# distortion-noise-and-ring-modulator-v1_0.net
KiCad netlist of a schematic drawn in EAGLE
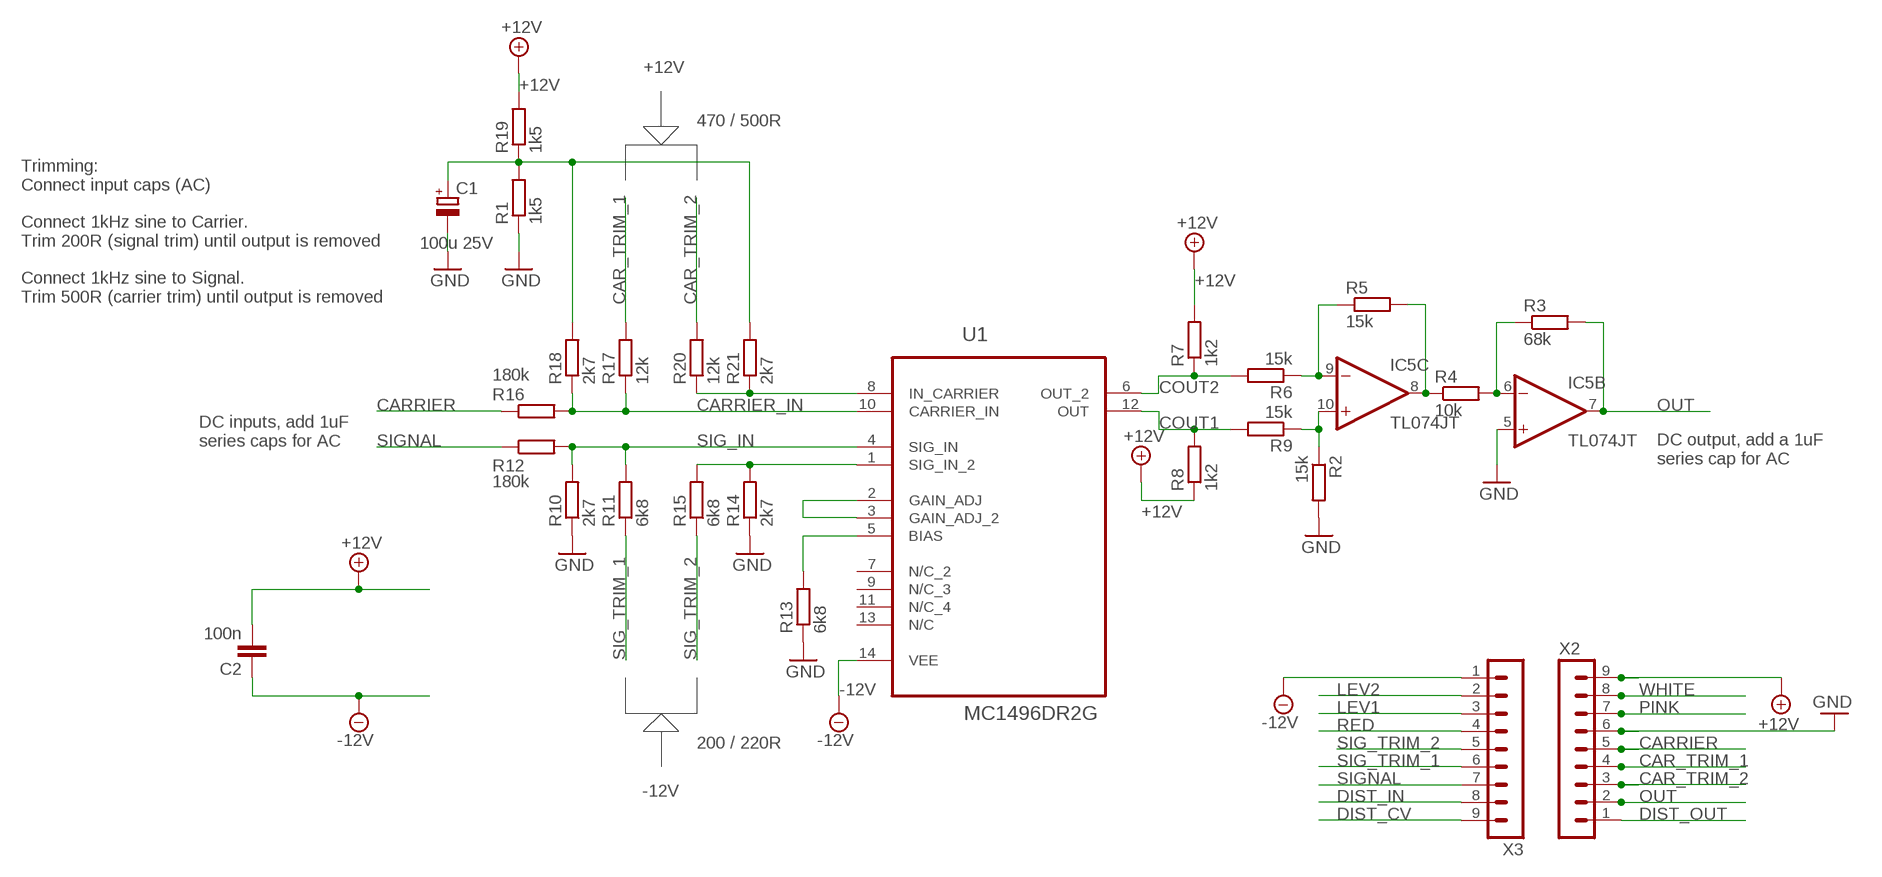
[diagram p0: schematic, sheet 1]
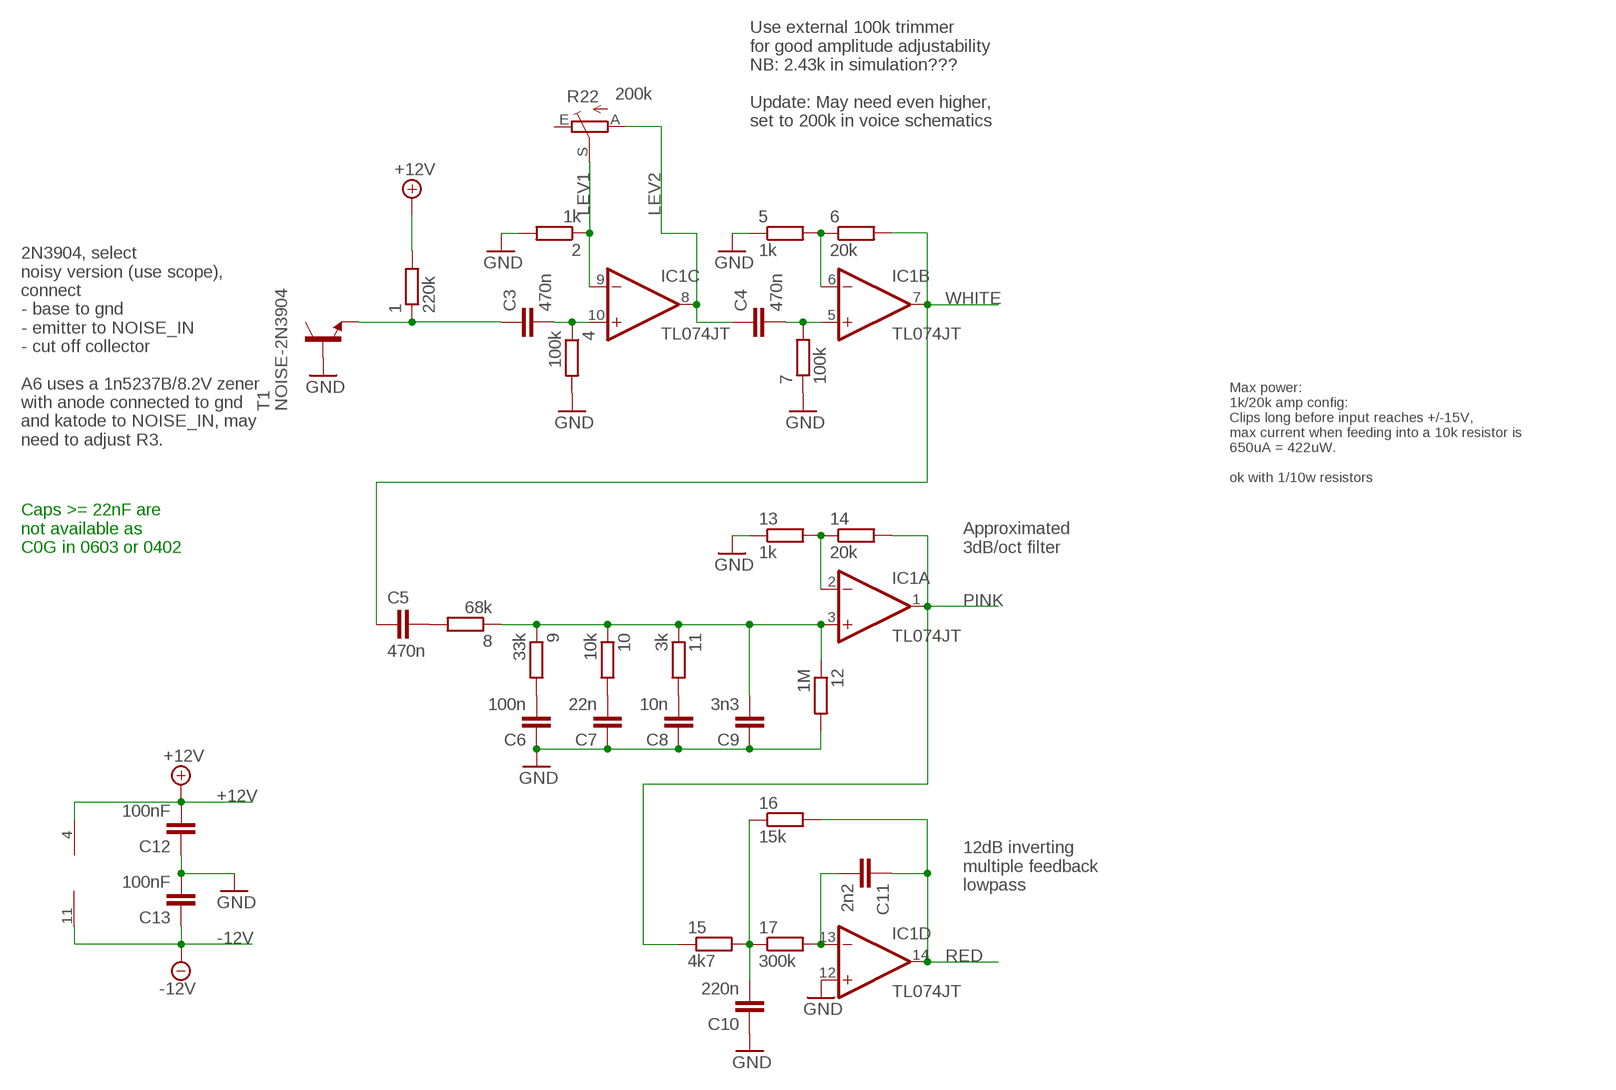
[diagram p1: schematic, sheet 2]
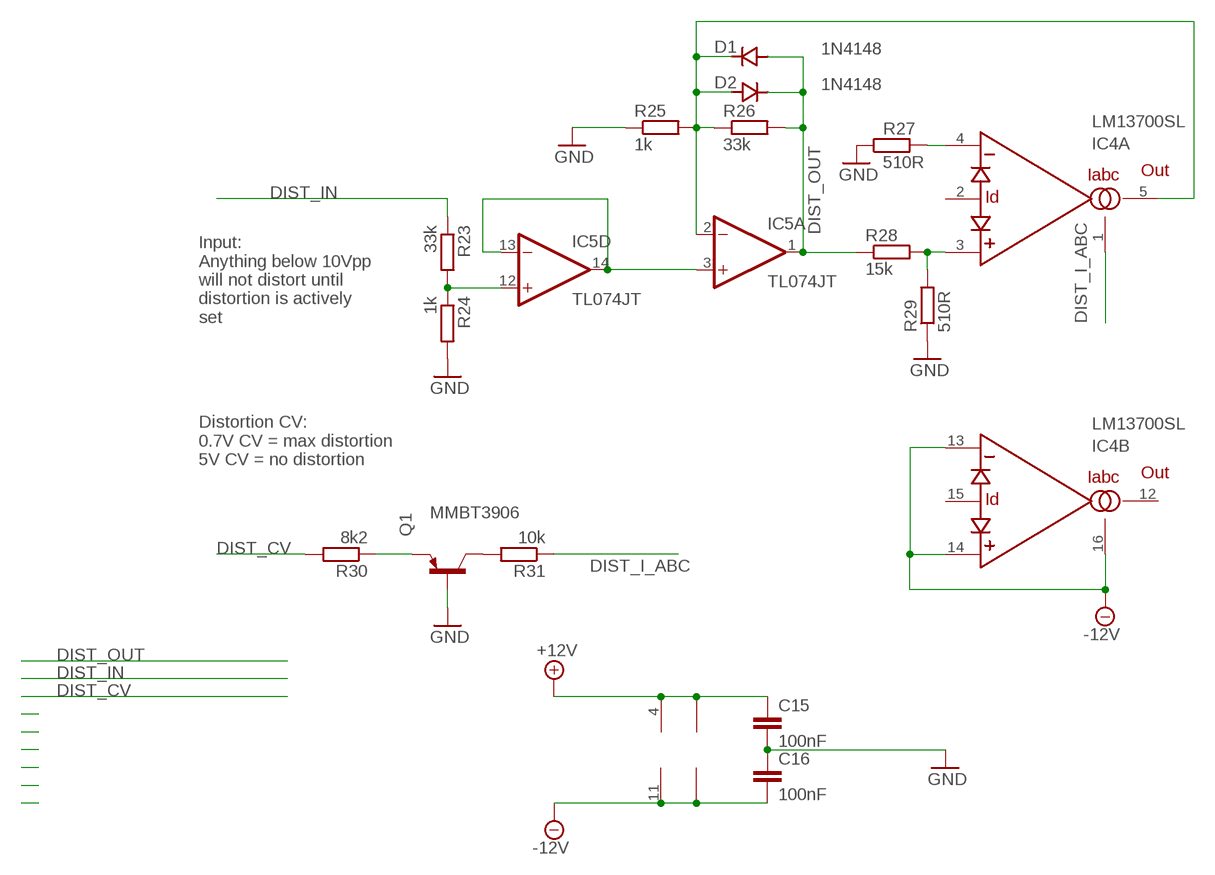
[diagram p2: schematic, sheet 3]

(export (version "E")
  (design (tool "Eeschema 10.0.6"))
  (components
    (comp (ref "1")
      (value "220k")
      (footprint "eagle-import:R0402")
      (libsource (lib "eagle-import") (part "R-EU_R0402"))
    )
    (comp (ref "2")
      (value "1k")
      (footprint "eagle-import:R0402")
      (libsource (lib "eagle-import") (part "R-EU_R0402"))
    )
    (comp (ref "4")
      (value "100k")
      (footprint "eagle-import:R0402")
      (libsource (lib "eagle-import") (part "R-EU_R0402"))
    )
    (comp (ref "5")
      (value "1k")
      (footprint "eagle-import:R0402")
      (libsource (lib "eagle-import") (part "R-EU_R0402"))
    )
    (comp (ref "6")
      (value "20k")
      (footprint "eagle-import:R0402")
      (libsource (lib "eagle-import") (part "R-EU_R0402"))
    )
    (comp (ref "7")
      (value "100k")
      (footprint "eagle-import:R0402")
      (libsource (lib "eagle-import") (part "R-EU_R0402"))
    )
    (comp (ref "8")
      (value "68k")
      (footprint "eagle-import:R0402")
      (libsource (lib "eagle-import") (part "R-EU_R0402"))
    )
    (comp (ref "9")
      (value "33k")
      (footprint "eagle-import:R0402")
      (libsource (lib "eagle-import") (part "R-EU_R0402"))
    )
    (comp (ref "10")
      (value "10k")
      (footprint "eagle-import:R0402")
      (libsource (lib "eagle-import") (part "R-EU_R0402"))
    )
    (comp (ref "11")
      (value "3k")
      (footprint "eagle-import:R0402")
      (libsource (lib "eagle-import") (part "R-EU_R0402"))
    )
    (comp (ref "12")
      (value "1M")
      (footprint "eagle-import:R0402")
      (libsource (lib "eagle-import") (part "R-EU_R0402"))
    )
    (comp (ref "13")
      (value "1k")
      (footprint "eagle-import:R0402")
      (libsource (lib "eagle-import") (part "R-EU_R0402"))
    )
    (comp (ref "14")
      (value "20k")
      (footprint "eagle-import:R0402")
      (libsource (lib "eagle-import") (part "R-EU_R0402"))
    )
    (comp (ref "15")
      (value "4k7")
      (footprint "eagle-import:R0402")
      (libsource (lib "eagle-import") (part "R-EU_R0402"))
    )
    (comp (ref "16")
      (value "15k")
      (footprint "eagle-import:R0402")
      (libsource (lib "eagle-import") (part "R-EU_R0402"))
    )
    (comp (ref "17")
      (value "300k")
      (footprint "eagle-import:R0402")
      (libsource (lib "eagle-import") (part "R-EU_R0402"))
    )
    (comp (ref "C3")
      (value "470n")
      (footprint "eagle-import:C0402-J")
      (libsource (lib "eagle-import") (part "C-EU-J"))
    )
    (comp (ref "C4")
      (value "470n")
      (footprint "eagle-import:C0402-J")
      (libsource (lib "eagle-import") (part "C-EU-J"))
    )
    (comp (ref "C5")
      (value "470n")
      (footprint "eagle-import:C0402-J")
      (libsource (lib "eagle-import") (part "C-EU-J"))
    )
    (comp (ref "C6")
      (value "100n")
      (footprint "eagle-import:C0402-J")
      (libsource (lib "eagle-import") (part "C-EU-J"))
    )
    (comp (ref "C7")
      (value "22n")
      (footprint "eagle-import:C0402-J")
      (libsource (lib "eagle-import") (part "C-EU-J"))
    )
    (comp (ref "C8")
      (value "10n")
      (footprint "eagle-import:C0402-J")
      (libsource (lib "eagle-import") (part "C-EU-J"))
    )
    (comp (ref "C9")
      (value "3n3")
      (footprint "eagle-import:C0402-J")
      (libsource (lib "eagle-import") (part "C-EU-J"))
    )
    (comp (ref "C10")
      (value "220n")
      (footprint "eagle-import:C0402-J")
      (libsource (lib "eagle-import") (part "C-EU-J"))
    )
    (comp (ref "C11")
      (value "2n2")
      (footprint "eagle-import:C0402-J")
      (libsource (lib "eagle-import") (part "C-EU-J"))
    )
    (comp (ref "C12")
      (value "100nF")
      (footprint "eagle-import:C0402-J")
      (libsource (lib "eagle-import") (part "C-EU-J"))
    )
    (comp (ref "C13")
      (value "100nF")
      (footprint "eagle-import:C0402-J")
      (libsource (lib "eagle-import") (part "C-EU-J"))
    )
    (comp (ref "IC1")
      (value "TL074JT")
      (footprint "eagle-import:TSSOP14J")
      (libsource (lib "eagle-import") (part "TL074JT"))
    )
    (comp (ref "R22")
      (value "200k")
      (footprint "eagle-import:S64W")
      (libsource (lib "eagle-import") (part "TRIM_EU-S64W"))
    )
    (comp (ref "T1")
      (value "NOISE-2N3904")
      (footprint "eagle-import:NOISE-2N3904-J")
      (libsource (lib "eagle-import") (part "NOISE-2N3904"))
    )
    (comp (ref "C1")
      (value "100u 25V")
      (footprint "eagle-import:UD-4X5,8_NICHICON")
      (libsource (lib "eagle-import") (part "CPOL-EUUD-4X5,8"))
    )
    (comp (ref "C2")
      (value "100n")
      (footprint "eagle-import:C0402-J")
      (libsource (lib "eagle-import") (part "C-EU-J"))
    )
    (comp (ref "IC5")
      (value "TL074JT")
      (footprint "eagle-import:TSSOP14J")
      (libsource (lib "eagle-import") (part "TL074JT"))
    )
    (comp (ref "R1")
      (value "1k5")
      (footprint "eagle-import:R0402")
      (libsource (lib "eagle-import") (part "R-EU_R0402"))
    )
    (comp (ref "R2")
      (value "15k")
      (footprint "eagle-import:R0402")
      (libsource (lib "eagle-import") (part "R-EU_R0402"))
    )
    (comp (ref "R3")
      (value "68k")
      (footprint "eagle-import:R0402")
      (libsource (lib "eagle-import") (part "R-EU_R0402"))
    )
    (comp (ref "R4")
      (value "10k")
      (footprint "eagle-import:R0402")
      (libsource (lib "eagle-import") (part "R-EU_R0402"))
    )
    (comp (ref "R5")
      (value "15k")
      (footprint "eagle-import:R0402")
      (libsource (lib "eagle-import") (part "R-EU_R0402"))
    )
    (comp (ref "R6")
      (value "15k")
      (footprint "eagle-import:R0402")
      (libsource (lib "eagle-import") (part "R-EU_R0402"))
    )
    (comp (ref "R7")
      (value "1k2")
      (footprint "eagle-import:R0402")
      (libsource (lib "eagle-import") (part "R-EU_R0402"))
    )
    (comp (ref "R8")
      (value "1k2")
      (footprint "eagle-import:R0402")
      (libsource (lib "eagle-import") (part "R-EU_R0402"))
    )
    (comp (ref "R9")
      (value "15k")
      (footprint "eagle-import:R0402")
      (libsource (lib "eagle-import") (part "R-EU_R0402"))
    )
    (comp (ref "R10")
      (value "2k7")
      (footprint "eagle-import:R0402")
      (libsource (lib "eagle-import") (part "R-EU_R0402"))
    )
    (comp (ref "R11")
      (value "6k8")
      (footprint "eagle-import:R0402")
      (libsource (lib "eagle-import") (part "R-EU_R0402"))
    )
    (comp (ref "R12")
      (value "180k")
      (footprint "eagle-import:R0402")
      (libsource (lib "eagle-import") (part "R-EU_R0402"))
    )
    (comp (ref "R13")
      (value "6k8")
      (footprint "eagle-import:R0402")
      (libsource (lib "eagle-import") (part "R-EU_R0402"))
    )
    (comp (ref "R14")
      (value "2k7")
      (footprint "eagle-import:R0402")
      (libsource (lib "eagle-import") (part "R-EU_R0402"))
    )
    (comp (ref "R15")
      (value "6k8")
      (footprint "eagle-import:R0402")
      (libsource (lib "eagle-import") (part "R-EU_R0402"))
    )
    (comp (ref "R16")
      (value "180k")
      (footprint "eagle-import:R0402")
      (libsource (lib "eagle-import") (part "R-EU_R0402"))
    )
    (comp (ref "R17")
      (value "12k")
      (footprint "eagle-import:R0402")
      (libsource (lib "eagle-import") (part "R-EU_R0402"))
    )
    (comp (ref "R18")
      (value "2k7")
      (footprint "eagle-import:R0402")
      (libsource (lib "eagle-import") (part "R-EU_R0402"))
    )
    (comp (ref "R19")
      (value "1k5")
      (footprint "eagle-import:R0402")
      (libsource (lib "eagle-import") (part "R-EU_R0402"))
    )
    (comp (ref "R20")
      (value "12k")
      (footprint "eagle-import:R0402")
      (libsource (lib "eagle-import") (part "R-EU_R0402"))
    )
    (comp (ref "R21")
      (value "2k7")
      (footprint "eagle-import:R0402")
      (libsource (lib "eagle-import") (part "R-EU_R0402"))
    )
    (comp (ref "U1")
      (value "MC1496DR2G")
      (footprint "eagle-import:SOIC127P600X175-14N")
      (libsource (lib "eagle-import") (part "MC1496DR2G"))
    )
    (comp (ref "X2")
      (value "MA09-1JN")
      (footprint "eagle-import:MA09N-1J")
      (libsource (lib "eagle-import") (part "MA09-1JN"))
    )
    (comp (ref "X3")
      (value "MA09-1JN")
      (footprint "eagle-import:MA09N-1J")
      (libsource (lib "eagle-import") (part "MA09-1JN"))
    )
    (comp (ref "C15")
      (value "100nF")
      (footprint "eagle-import:C0402-J")
      (libsource (lib "eagle-import") (part "C-EU-J"))
    )
    (comp (ref "C16")
      (value "100nF")
      (footprint "eagle-import:C0402-J")
      (libsource (lib "eagle-import") (part "C-EU-J"))
    )
    (comp (ref "D1")
      (value "1N4148")
      (footprint "eagle-import:SOD323J")
      (libsource (lib "eagle-import") (part "1N4148SOD323"))
    )
    (comp (ref "D2")
      (value "1N4148")
      (footprint "eagle-import:SOD323J")
      (libsource (lib "eagle-import") (part "1N4148SOD323"))
    )
    (comp (ref "IC4")
      (value "LM13700SL")
      (footprint "eagle-import:SO16-NARROW-J")
      (libsource (lib "eagle-import") (part "LM13700SL"))
    )
    (comp (ref "Q1")
      (value "MMBT3906")
      (footprint "eagle-import:SOT23-BEC")
      (libsource (lib "eagle-import") (part "MMBT3906SMDLT1"))
    )
    (comp (ref "R23")
      (value "33k")
      (footprint "eagle-import:R0402")
      (libsource (lib "eagle-import") (part "R-EU_R0402"))
    )
    (comp (ref "R24")
      (value "1k")
      (footprint "eagle-import:R0402")
      (libsource (lib "eagle-import") (part "R-EU_R0402"))
    )
    (comp (ref "R25")
      (value "1k")
      (footprint "eagle-import:R0402")
      (libsource (lib "eagle-import") (part "R-EU_R0402"))
    )
    (comp (ref "R26")
      (value "33k")
      (footprint "eagle-import:R0402")
      (libsource (lib "eagle-import") (part "R-EU_R0402"))
    )
    (comp (ref "R27")
      (value "510R")
      (footprint "eagle-import:R0402")
      (libsource (lib "eagle-import") (part "R-EU_R0402"))
    )
    (comp (ref "R28")
      (value "15k")
      (footprint "eagle-import:R0402")
      (libsource (lib "eagle-import") (part "R-EU_R0402"))
    )
    (comp (ref "R29")
      (value "510R")
      (footprint "eagle-import:R0402")
      (libsource (lib "eagle-import") (part "R-EU_R0402"))
    )
    (comp (ref "R30")
      (value "8k2")
      (footprint "eagle-import:R0402")
      (libsource (lib "eagle-import") (part "R-EU_R0402"))
    )
    (comp (ref "R31")
      (value "10k")
      (footprint "eagle-import:R0402")
      (libsource (lib "eagle-import") (part "R-EU_R0402"))
    )
  )
  (nets
    (net (code "1") (name "+12V") (class "Default")
      (node (ref "1") (pin "2") (pinfunction "2_2") (pintype "passive"))
      (node (ref "C12") (pin "2") (pinfunction "2_2") (pintype "passive"))
      (node (ref "C15") (pin "1") (pinfunction "1_1") (pintype "passive"))
      (node (ref "C2") (pin "2") (pinfunction "2_2") (pintype "passive"))
      (node (ref "IC1") (pin "4") (pinfunction "V+_4") (pintype "power_in"))
      (node (ref "IC4") (pin "11") (pinfunction "V+_11") (pintype "bidirectional"))
      (node (ref "IC5") (pin "4") (pinfunction "V+_4") (pintype "power_in"))
      (node (ref "R19") (pin "2") (pinfunction "2_2") (pintype "passive"))
      (node (ref "R7") (pin "2") (pinfunction "2_2") (pintype "passive"))
      (node (ref "R8") (pin "1") (pinfunction "1_1") (pintype "passive"))
      (node (ref "X2") (pin "9") (pinfunction "9_9") (pintype "passive"))
    )
    (net (code "2") (name "-12V") (class "Default")
      (node (ref "C13") (pin "1") (pinfunction "1_1") (pintype "passive"))
      (node (ref "C16") (pin "2") (pinfunction "2_2") (pintype "passive"))
      (node (ref "C2") (pin "1") (pinfunction "1_1") (pintype "passive"))
      (node (ref "IC1") (pin "11") (pinfunction "V-_11") (pintype "power_in"))
      (node (ref "IC4") (pin "13") (pinfunction "-IN_13") (pintype "bidirectional"))
      (node (ref "IC4") (pin "14") (pinfunction "+IN_14") (pintype "bidirectional"))
      (node (ref "IC4") (pin "16") (pinfunction "IABC_16") (pintype "bidirectional"))
      (node (ref "IC4") (pin "6") (pinfunction "V-_6") (pintype "bidirectional"))
      (node (ref "IC5") (pin "11") (pinfunction "V-_11") (pintype "power_in"))
      (node (ref "U1") (pin "14") (pinfunction "VEE_14") (pintype "passive"))
      (node (ref "X3") (pin "1") (pinfunction "1_1") (pintype "passive"))
    )
    (net (code "3") (name "CARRIER") (class "Default")
      (node (ref "R16") (pin "1") (pinfunction "1_1") (pintype "passive"))
      (node (ref "X2") (pin "5") (pinfunction "5_5") (pintype "passive"))
    )
    (net (code "4") (name "CARRIER_IN") (class "Default")
      (node (ref "R16") (pin "2") (pinfunction "2_2") (pintype "passive"))
      (node (ref "R17") (pin "1") (pinfunction "1_1") (pintype "passive"))
      (node (ref "R18") (pin "1") (pinfunction "1_1") (pintype "passive"))
      (node (ref "U1") (pin "10") (pinfunction "CARRIER_IN_10") (pintype "power_in"))
    )
    (net (code "5") (name "CAR_TRIM_1") (class "Default")
      (node (ref "R17") (pin "2") (pinfunction "2_2") (pintype "passive"))
      (node (ref "X2") (pin "4") (pinfunction "4_4") (pintype "passive"))
    )
    (net (code "6") (name "CAR_TRIM_2") (class "Default")
      (node (ref "R20") (pin "2") (pinfunction "2_2") (pintype "passive"))
      (node (ref "X2") (pin "3") (pinfunction "3_3") (pintype "passive"))
    )
    (net (code "7") (name "COUT1") (class "Default")
      (node (ref "R8") (pin "2") (pinfunction "2_2") (pintype "passive"))
      (node (ref "R9") (pin "2") (pinfunction "2_2") (pintype "passive"))
      (node (ref "U1") (pin "12") (pinfunction "OUT_12") (pintype "output"))
    )
    (net (code "8") (name "COUT2") (class "Default")
      (node (ref "R6") (pin "2") (pinfunction "2_2") (pintype "passive"))
      (node (ref "R7") (pin "1") (pinfunction "1_1") (pintype "passive"))
      (node (ref "U1") (pin "6") (pinfunction "OUT_2_6") (pintype "output"))
    )
    (net (code "9") (name "DIST_CV") (class "Default")
      (node (ref "R30") (pin "2") (pinfunction "2_2") (pintype "passive"))
      (node (ref "X3") (pin "9") (pinfunction "9_9") (pintype "passive"))
    )
    (net (code "10") (name "DIST_IN") (class "Default")
      (node (ref "R23") (pin "1") (pinfunction "1_1") (pintype "passive"))
      (node (ref "X3") (pin "8") (pinfunction "8_8") (pintype "passive"))
    )
    (net (code "11") (name "DIST_I_ABC") (class "Default")
      (node (ref "IC4") (pin "1") (pinfunction "IABC_1") (pintype "bidirectional"))
      (node (ref "R31") (pin "1") (pinfunction "1_1") (pintype "passive"))
    )
    (net (code "12") (name "DIST_OUT") (class "Default")
      (node (ref "D1") (pin "2") (pinfunction "A_2") (pintype "passive"))
      (node (ref "D2") (pin "1") (pinfunction "C_1") (pintype "passive"))
      (node (ref "IC5") (pin "1") (pinfunction "OUT_1") (pintype "output"))
      (node (ref "R26") (pin "2") (pinfunction "2_2") (pintype "passive"))
      (node (ref "R28") (pin "1") (pinfunction "1_1") (pintype "passive"))
      (node (ref "X2") (pin "1") (pinfunction "1_1") (pintype "passive"))
    )
    (net (code "13") (name "GND") (class "Default")
      (node (ref "12") (pin "2") (pinfunction "2_2") (pintype "passive"))
      (node (ref "13") (pin "1") (pinfunction "1_1") (pintype "passive"))
      (node (ref "2") (pin "2") (pinfunction "2_2") (pintype "passive"))
      (node (ref "4") (pin "2") (pinfunction "2_2") (pintype "passive"))
      (node (ref "5") (pin "1") (pinfunction "1_1") (pintype "passive"))
      (node (ref "7") (pin "1") (pinfunction "1_1") (pintype "passive"))
      (node (ref "C1") (pin "-") (pinfunction "-_-") (pintype "passive"))
      (node (ref "C10") (pin "1") (pinfunction "1_1") (pintype "passive"))
      (node (ref "C12") (pin "1") (pinfunction "1_1") (pintype "passive"))
      (node (ref "C13") (pin "2") (pinfunction "2_2") (pintype "passive"))
      (node (ref "C15") (pin "2") (pinfunction "2_2") (pintype "passive"))
      (node (ref "C16") (pin "1") (pinfunction "1_1") (pintype "passive"))
      (node (ref "C6") (pin "1") (pinfunction "1_1") (pintype "passive"))
      (node (ref "C7") (pin "1") (pinfunction "1_1") (pintype "passive"))
      (node (ref "C8") (pin "1") (pinfunction "1_1") (pintype "passive"))
      (node (ref "C9") (pin "1") (pinfunction "1_1") (pintype "passive"))
      (node (ref "IC1") (pin "12") (pinfunction "+IN_12") (pintype "input"))
      (node (ref "IC5") (pin "5") (pinfunction "+IN_5") (pintype "input"))
      (node (ref "Q1") (pin "B") (pinfunction "B_B") (pintype "passive"))
      (node (ref "R1") (pin "1") (pinfunction "1_1") (pintype "passive"))
      (node (ref "R10") (pin "1") (pinfunction "1_1") (pintype "passive"))
      (node (ref "R13") (pin "1") (pinfunction "1_1") (pintype "passive"))
      (node (ref "R14") (pin "1") (pinfunction "1_1") (pintype "passive"))
      (node (ref "R2") (pin "2") (pinfunction "2_2") (pintype "passive"))
      (node (ref "R24") (pin "2") (pinfunction "2_2") (pintype "passive"))
      (node (ref "R25") (pin "1") (pinfunction "1_1") (pintype "passive"))
      (node (ref "R27") (pin "1") (pinfunction "1_1") (pintype "passive"))
      (node (ref "R29") (pin "1") (pinfunction "1_1") (pintype "passive"))
      (node (ref "T1") (pin "B") (pinfunction "B_B") (pintype "passive"))
      (node (ref "X2") (pin "6") (pinfunction "6_6") (pintype "passive"))
    )
    (net (code "14") (name "LEV1") (class "Default")
      (node (ref "2") (pin "1") (pinfunction "1_1") (pintype "passive"))
      (node (ref "IC1") (pin "9") (pinfunction "-IN_9") (pintype "input"))
      (node (ref "R22") (pin "S") (pinfunction "S_S") (pintype "passive"))
      (node (ref "X3") (pin "3") (pinfunction "3_3") (pintype "passive"))
    )
    (net (code "15") (name "LEV2") (class "Default")
      (node (ref "C4") (pin "1") (pinfunction "1_1") (pintype "passive"))
      (node (ref "IC1") (pin "8") (pinfunction "OUT_8") (pintype "output"))
      (node (ref "R22") (pin "A") (pinfunction "A_A") (pintype "passive"))
      (node (ref "X3") (pin "2") (pinfunction "2_2") (pintype "passive"))
    )
    (net (code "16") (name "Net-(1-Pad1)") (class "Default")
      (node (ref "1") (pin "1") (pinfunction "1_1") (pintype "passive"))
      (node (ref "C3") (pin "1") (pinfunction "1_1") (pintype "passive"))
      (node (ref "T1") (pin "E") (pinfunction "E_E") (pintype "passive"))
    )
    (net (code "17") (name "Net-(8-Pad2)") (class "Default")
      (node (ref "8") (pin "2") (pinfunction "2_2") (pintype "passive"))
      (node (ref "C5") (pin "2") (pinfunction "2_2") (pintype "passive"))
    )
    (net (code "18") (name "Net-(9-Pad2)") (class "Default")
      (node (ref "9") (pin "2") (pinfunction "2_2") (pintype "passive"))
      (node (ref "C6") (pin "2") (pinfunction "2_2") (pintype "passive"))
    )
    (net (code "19") (name "Net-(10-Pad2)") (class "Default")
      (node (ref "10") (pin "2") (pinfunction "2_2") (pintype "passive"))
      (node (ref "C7") (pin "2") (pinfunction "2_2") (pintype "passive"))
    )
    (net (code "20") (name "Net-(11-Pad2)") (class "Default")
      (node (ref "11") (pin "2") (pinfunction "2_2") (pintype "passive"))
      (node (ref "C8") (pin "2") (pinfunction "2_2") (pintype "passive"))
    )
    (net (code "21") (name "Net-(15-Pad2)") (class "Default")
      (node (ref "15") (pin "2") (pinfunction "2_2") (pintype "passive"))
      (node (ref "16") (pin "1") (pinfunction "1_1") (pintype "passive"))
      (node (ref "17") (pin "1") (pinfunction "1_1") (pintype "passive"))
      (node (ref "C10") (pin "2") (pinfunction "2_2") (pintype "passive"))
    )
    (net (code "22") (name "Net-(C1-Pad+)") (class "Default")
      (node (ref "C1") (pin "+") (pinfunction "+_+") (pintype "passive"))
      (node (ref "R1") (pin "2") (pinfunction "2_2") (pintype "passive"))
      (node (ref "R18") (pin "2") (pinfunction "2_2") (pintype "passive"))
      (node (ref "R19") (pin "1") (pinfunction "1_1") (pintype "passive"))
      (node (ref "R21") (pin "2") (pinfunction "2_2") (pintype "passive"))
    )
    (net (code "23") (name "Net-(D1-C)") (class "Default")
      (node (ref "D1") (pin "1") (pinfunction "C_1") (pintype "passive"))
      (node (ref "D2") (pin "2") (pinfunction "A_2") (pintype "passive"))
      (node (ref "IC4") (pin "5") (pinfunction "OUT_5") (pintype "bidirectional"))
      (node (ref "IC5") (pin "2") (pinfunction "-IN_2") (pintype "input"))
      (node (ref "R25") (pin "2") (pinfunction "2_2") (pintype "passive"))
      (node (ref "R26") (pin "1") (pinfunction "1_1") (pintype "passive"))
    )
    (net (code "24") (name "Net-(IC1A-+IN)") (class "Default")
      (node (ref "10") (pin "1") (pinfunction "1_1") (pintype "passive"))
      (node (ref "11") (pin "1") (pinfunction "1_1") (pintype "passive"))
      (node (ref "12") (pin "1") (pinfunction "1_1") (pintype "passive"))
      (node (ref "8") (pin "1") (pinfunction "1_1") (pintype "passive"))
      (node (ref "9") (pin "1") (pinfunction "1_1") (pintype "passive"))
      (node (ref "C9") (pin "2") (pinfunction "2_2") (pintype "passive"))
      (node (ref "IC1") (pin "3") (pinfunction "+IN_3") (pintype "input"))
    )
    (net (code "25") (name "Net-(IC1A--IN)") (class "Default")
      (node (ref "13") (pin "2") (pinfunction "2_2") (pintype "passive"))
      (node (ref "14") (pin "1") (pinfunction "1_1") (pintype "passive"))
      (node (ref "IC1") (pin "2") (pinfunction "-IN_2") (pintype "input"))
    )
    (net (code "26") (name "Net-(IC1B-+IN)") (class "Default")
      (node (ref "7") (pin "2") (pinfunction "2_2") (pintype "passive"))
      (node (ref "C4") (pin "2") (pinfunction "2_2") (pintype "passive"))
      (node (ref "IC1") (pin "5") (pinfunction "+IN_5") (pintype "input"))
    )
    (net (code "27") (name "Net-(IC1B--IN)") (class "Default")
      (node (ref "5") (pin "2") (pinfunction "2_2") (pintype "passive"))
      (node (ref "6") (pin "1") (pinfunction "1_1") (pintype "passive"))
      (node (ref "IC1") (pin "6") (pinfunction "-IN_6") (pintype "input"))
    )
    (net (code "28") (name "Net-(IC1C-+IN)") (class "Default")
      (node (ref "4") (pin "1") (pinfunction "1_1") (pintype "passive"))
      (node (ref "C3") (pin "2") (pinfunction "2_2") (pintype "passive"))
      (node (ref "IC1") (pin "10") (pinfunction "+IN_10") (pintype "input"))
    )
    (net (code "29") (name "Net-(IC1D--IN)") (class "Default")
      (node (ref "17") (pin "2") (pinfunction "2_2") (pintype "passive"))
      (node (ref "C11") (pin "2") (pinfunction "2_2") (pintype "passive"))
      (node (ref "IC1") (pin "13") (pinfunction "-IN_13") (pintype "input"))
    )
    (net (code "30") (name "Net-(IC4A-+IN)") (class "Default")
      (node (ref "IC4") (pin "3") (pinfunction "+IN_3") (pintype "bidirectional"))
      (node (ref "R28") (pin "2") (pinfunction "2_2") (pintype "passive"))
      (node (ref "R29") (pin "2") (pinfunction "2_2") (pintype "passive"))
    )
    (net (code "31") (name "Net-(IC4A--IN)") (class "Default")
      (node (ref "IC4") (pin "4") (pinfunction "-IN_4") (pintype "bidirectional"))
      (node (ref "R27") (pin "2") (pinfunction "2_2") (pintype "passive"))
    )
    (net (code "32") (name "Net-(IC5A-+IN)") (class "Default")
      (node (ref "IC5") (pin "13") (pinfunction "-IN_13") (pintype "input"))
      (node (ref "IC5") (pin "14") (pinfunction "OUT_14") (pintype "output"))
      (node (ref "IC5") (pin "3") (pinfunction "+IN_3") (pintype "input"))
    )
    (net (code "33") (name "Net-(IC5B--IN)") (class "Default")
      (node (ref "IC5") (pin "6") (pinfunction "-IN_6") (pintype "input"))
      (node (ref "R3") (pin "1") (pinfunction "1_1") (pintype "passive"))
      (node (ref "R4") (pin "2") (pinfunction "2_2") (pintype "passive"))
    )
    (net (code "34") (name "Net-(IC5C-+IN)") (class "Default")
      (node (ref "IC5") (pin "10") (pinfunction "+IN_10") (pintype "input"))
      (node (ref "R2") (pin "1") (pinfunction "1_1") (pintype "passive"))
      (node (ref "R9") (pin "1") (pinfunction "1_1") (pintype "passive"))
    )
    (net (code "35") (name "Net-(IC5C--IN)") (class "Default")
      (node (ref "IC5") (pin "9") (pinfunction "-IN_9") (pintype "input"))
      (node (ref "R5") (pin "1") (pinfunction "1_1") (pintype "passive"))
      (node (ref "R6") (pin "1") (pinfunction "1_1") (pintype "passive"))
    )
    (net (code "36") (name "Net-(IC5C-OUT)") (class "Default")
      (node (ref "IC5") (pin "8") (pinfunction "OUT_8") (pintype "output"))
      (node (ref "R4") (pin "1") (pinfunction "1_1") (pintype "passive"))
      (node (ref "R5") (pin "2") (pinfunction "2_2") (pintype "passive"))
    )
    (net (code "37") (name "Net-(IC5D-+IN)") (class "Default")
      (node (ref "IC5") (pin "12") (pinfunction "+IN_12") (pintype "input"))
      (node (ref "R23") (pin "2") (pinfunction "2_2") (pintype "passive"))
      (node (ref "R24") (pin "1") (pinfunction "1_1") (pintype "passive"))
    )
    (net (code "38") (name "Net-(Q1-PadC)") (class "Default")
      (node (ref "Q1") (pin "C") (pinfunction "C_C") (pintype "passive"))
      (node (ref "R31") (pin "2") (pinfunction "2_2") (pintype "passive"))
    )
    (net (code "39") (name "Net-(Q1-PadE)") (class "Default")
      (node (ref "Q1") (pin "E") (pinfunction "E_E") (pintype "passive"))
      (node (ref "R30") (pin "1") (pinfunction "1_1") (pintype "passive"))
    )
    (net (code "40") (name "Net-(U1-BIAS)") (class "Default")
      (node (ref "R13") (pin "2") (pinfunction "2_2") (pintype "passive"))
      (node (ref "U1") (pin "5") (pinfunction "BIAS_5") (pintype "input"))
    )
    (net (code "41") (name "Net-(U1-GAIN_ADJ)") (class "Default")
      (node (ref "U1") (pin "2") (pinfunction "GAIN_ADJ_2") (pintype "input"))
      (node (ref "U1") (pin "3") (pinfunction "GAIN_ADJ_2_3") (pintype "input"))
    )
    (net (code "42") (name "Net-(U1-IN_CARRIER)") (class "Default")
      (node (ref "R20") (pin "1") (pinfunction "1_1") (pintype "passive"))
      (node (ref "R21") (pin "1") (pinfunction "1_1") (pintype "passive"))
      (node (ref "U1") (pin "8") (pinfunction "IN_CARRIER_8") (pintype "power_in"))
    )
    (net (code "43") (name "Net-(U1-SIG_IN_2)") (class "Default")
      (node (ref "R14") (pin "2") (pinfunction "2_2") (pintype "passive"))
      (node (ref "R15") (pin "2") (pinfunction "2_2") (pintype "passive"))
      (node (ref "U1") (pin "1") (pinfunction "SIG_IN_2_1") (pintype "input"))
    )
    (net (code "44") (name "OUT") (class "Default")
      (node (ref "IC5") (pin "7") (pinfunction "OUT_7") (pintype "output"))
      (node (ref "R3") (pin "2") (pinfunction "2_2") (pintype "passive"))
      (node (ref "X2") (pin "2") (pinfunction "2_2") (pintype "passive"))
    )
    (net (code "45") (name "PINK") (class "Default")
      (node (ref "14") (pin "2") (pinfunction "2_2") (pintype "passive"))
      (node (ref "15") (pin "1") (pinfunction "1_1") (pintype "passive"))
      (node (ref "IC1") (pin "1") (pinfunction "OUT_1") (pintype "output"))
      (node (ref "X2") (pin "7") (pinfunction "7_7") (pintype "passive"))
    )
    (net (code "46") (name "RED") (class "Default")
      (node (ref "16") (pin "2") (pinfunction "2_2") (pintype "passive"))
      (node (ref "C11") (pin "1") (pinfunction "1_1") (pintype "passive"))
      (node (ref "IC1") (pin "14") (pinfunction "OUT_14") (pintype "output"))
      (node (ref "X3") (pin "4") (pinfunction "4_4") (pintype "passive"))
    )
    (net (code "47") (name "SIGNAL") (class "Default")
      (node (ref "R12") (pin "1") (pinfunction "1_1") (pintype "passive"))
      (node (ref "X3") (pin "7") (pinfunction "7_7") (pintype "passive"))
    )
    (net (code "48") (name "SIG_IN") (class "Default")
      (node (ref "R10") (pin "2") (pinfunction "2_2") (pintype "passive"))
      (node (ref "R11") (pin "2") (pinfunction "2_2") (pintype "passive"))
      (node (ref "R12") (pin "2") (pinfunction "2_2") (pintype "passive"))
      (node (ref "U1") (pin "4") (pinfunction "SIG_IN_4") (pintype "input"))
    )
    (net (code "49") (name "SIG_TRIM_1") (class "Default")
      (node (ref "R11") (pin "1") (pinfunction "1_1") (pintype "passive"))
      (node (ref "X3") (pin "6") (pinfunction "6_6") (pintype "passive"))
    )
    (net (code "50") (name "SIG_TRIM_2") (class "Default")
      (node (ref "R15") (pin "1") (pinfunction "1_1") (pintype "passive"))
      (node (ref "X3") (pin "5") (pinfunction "5_5") (pintype "passive"))
    )
    (net (code "51") (name "WHITE") (class "Default")
      (node (ref "6") (pin "2") (pinfunction "2_2") (pintype "passive"))
      (node (ref "C5") (pin "1") (pinfunction "1_1") (pintype "passive"))
      (node (ref "IC1") (pin "7") (pinfunction "OUT_7") (pintype "output"))
      (node (ref "X2") (pin "8") (pinfunction "8_8") (pintype "passive"))
    )
    (net (code "52") (name "unconnected-(IC4A-ID-Pad2)") (class "Default")
      (node (ref "IC4") (pin "2") (pinfunction "ID_2") (pintype "bidirectional"))
    )
    (net (code "53") (name "unconnected-(IC4B-ID-Pad15)") (class "Default")
      (node (ref "IC4") (pin "15") (pinfunction "ID_15") (pintype "bidirectional"))
    )
    (net (code "54") (name "unconnected-(IC4B-OUT-Pad12)") (class "Default")
      (node (ref "IC4") (pin "12") (pinfunction "OUT_12") (pintype "bidirectional"))
    )
    (net (code "55") (name "unconnected-(R22-PadE)") (class "Default")
      (node (ref "R22") (pin "E") (pinfunction "E_E") (pintype "passive"))
    )
    (net (code "56") (name "unconnected-(U1-N{slash}C-Pad13)") (class "Default")
      (node (ref "U1") (pin "13") (pinfunction "N/C_13") (pintype "no_connect"))
    )
    (net (code "57") (name "unconnected-(U1-N{slash}C_2-Pad7)") (class "Default")
      (node (ref "U1") (pin "7") (pinfunction "N/C_2_7") (pintype "no_connect"))
    )
    (net (code "58") (name "unconnected-(U1-N{slash}C_3-Pad9)") (class "Default")
      (node (ref "U1") (pin "9") (pinfunction "N/C_3_9") (pintype "no_connect"))
    )
    (net (code "59") (name "unconnected-(U1-N{slash}C_4-Pad11)") (class "Default")
      (node (ref "U1") (pin "11") (pinfunction "N/C_4_11") (pintype "no_connect"))
    )
  )
)
